# LB_BIT_i7-remoteTrigger_v03_2_2.net
KiCad netlist of a schematic drawn in EAGLE
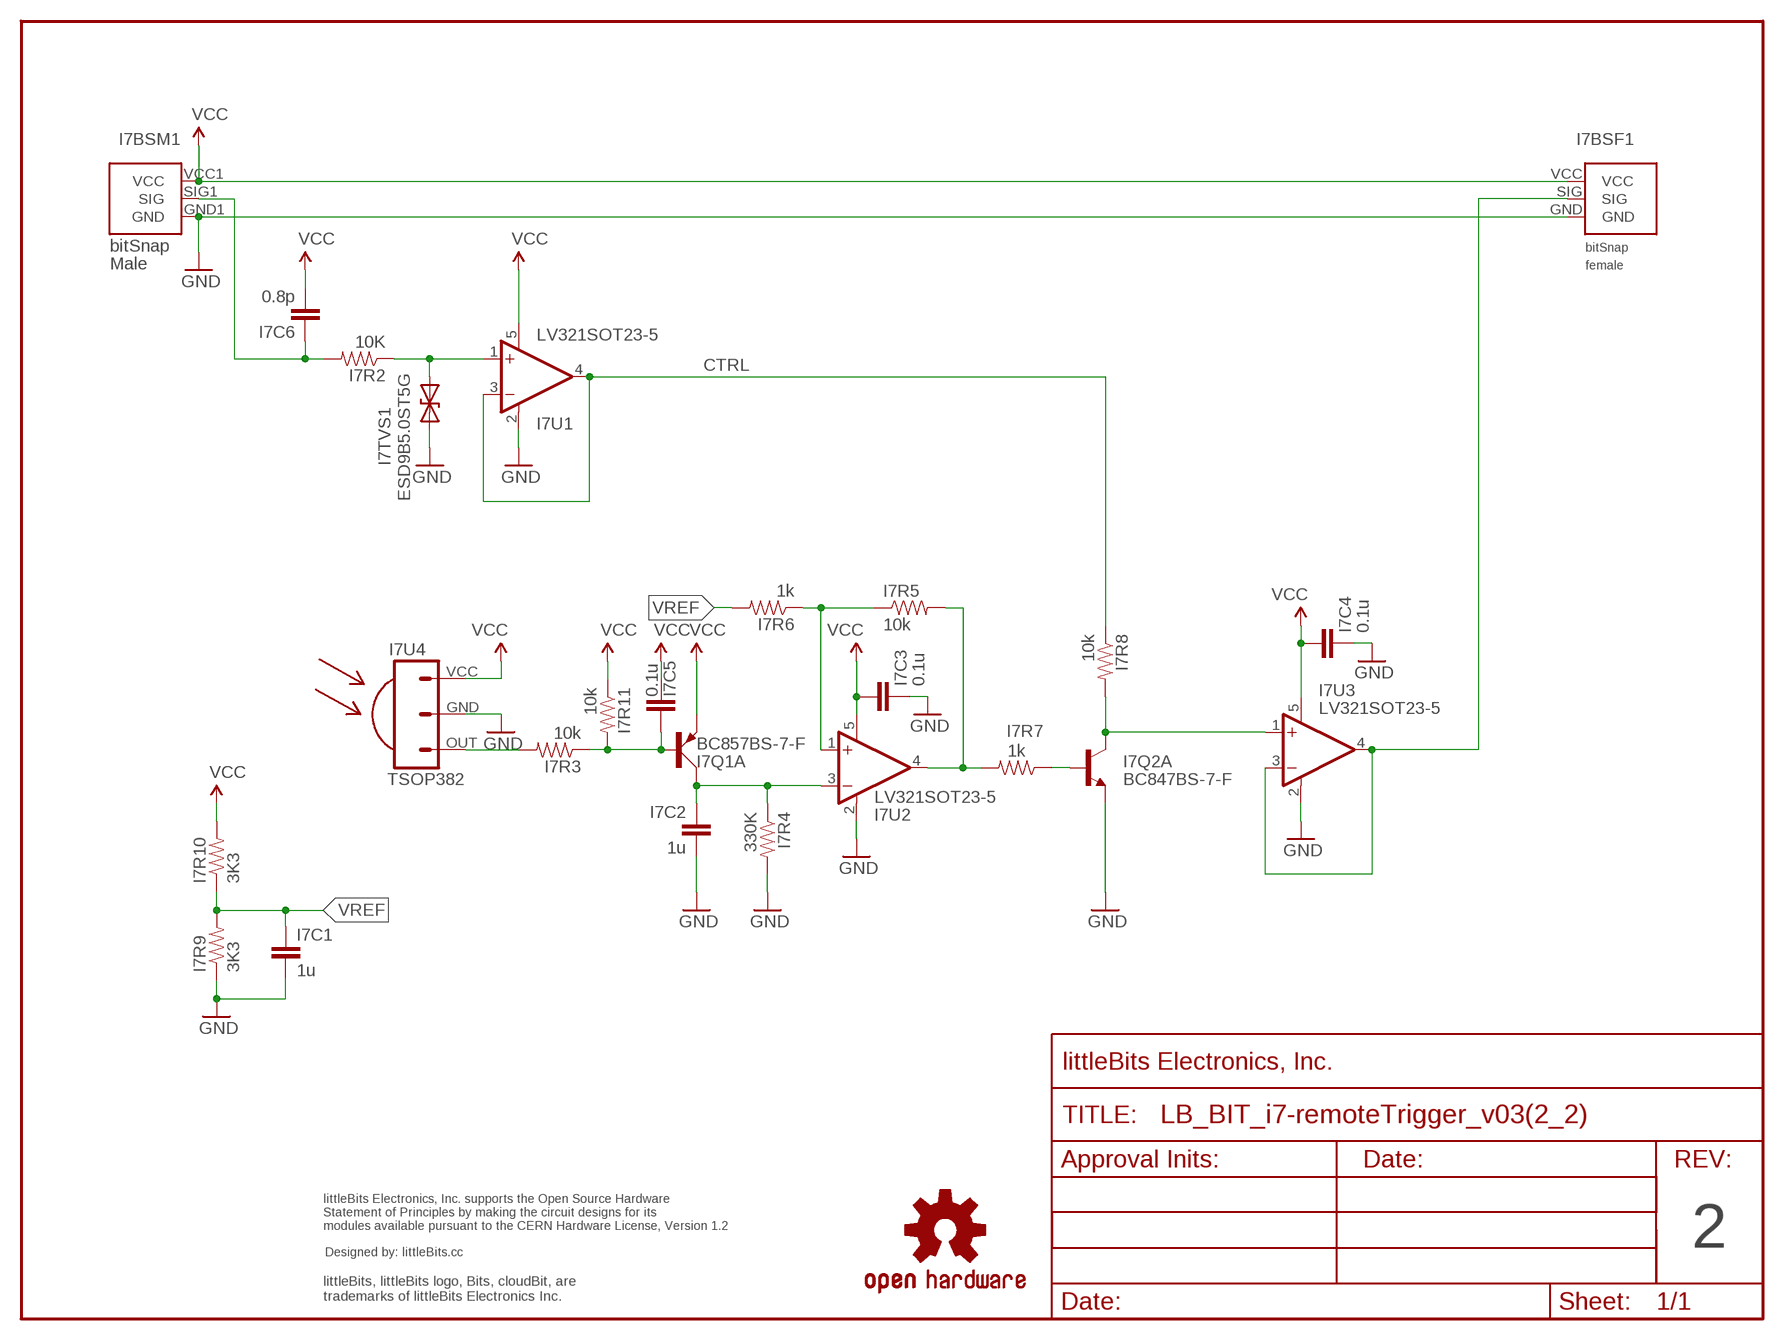
[diagram p0: schematic, sheet 1]

(export (version "E")
  (design (tool "Eeschema 10.0.6"))
  (components
    (comp (ref "I7BSF1")
      (value "BITSNAP_V03_FEMALE")
      (footprint "eagle-import:BITSNAP_V03_FEMALE")
      (libsource (lib "eagle-import") (part "BITSNAP_V03_FEMALE"))
    )
    (comp (ref "I7BSM1")
      (value "BITSNAP_V03_MALE")
      (footprint "eagle-import:BITSNAP_V03_MALE")
      (libsource (lib "eagle-import") (part "BITSNAP_V03_MALE"))
    )
    (comp (ref "I7C1")
      (value "1u")
      (footprint "eagle-import:CAP-0603")
      (libsource (lib "eagle-import") (part "CAPCAP-0603"))
    )
    (comp (ref "I7C2")
      (value "1u")
      (footprint "eagle-import:CAP-0603")
      (libsource (lib "eagle-import") (part "CAPCAP-0603"))
    )
    (comp (ref "I7C3")
      (value "0.1u")
      (footprint "eagle-import:CAP-0603")
      (libsource (lib "eagle-import") (part "CAPCAP-0603"))
    )
    (comp (ref "I7C4")
      (value "0.1u")
      (footprint "eagle-import:CAP-0603")
      (libsource (lib "eagle-import") (part "CAPCAP-0603"))
    )
    (comp (ref "I7C5")
      (value "0.1u")
      (footprint "eagle-import:CAP-0603")
      (libsource (lib "eagle-import") (part "CAPCAP-0603"))
    )
    (comp (ref "I7C6")
      (value "0.8p")
      (footprint "eagle-import:CAP-0603")
      (libsource (lib "eagle-import") (part "CAPCAP-0603"))
    )
    (comp (ref "I7Q1")
      (value "BC857BS-7-F")
      (footprint "eagle-import:SOT-363_PHILLIPS")
      (libsource (lib "eagle-import") (part "TRANS-BJT_PNP-DUALBC857"))
    )
    (comp (ref "I7Q2")
      (value "BC847BS-7-F")
      (footprint "eagle-import:SOT-363_PHILLIPS")
      (libsource (lib "eagle-import") (part "TRANS-BJT_NPN-DUAL-BC847BS"))
    )
    (comp (ref "I7R2")
      (value "10K")
      (footprint "eagle-import:RES-0603")
      (libsource (lib "eagle-import") (part "RESISTOR0603"))
    )
    (comp (ref "I7R3")
      (value "10k")
      (footprint "eagle-import:RES-0603")
      (libsource (lib "eagle-import") (part "RESISTOR0603"))
    )
    (comp (ref "I7R4")
      (value "330K")
      (footprint "eagle-import:RES-0603")
      (libsource (lib "eagle-import") (part "RESISTOR0603"))
    )
    (comp (ref "I7R5")
      (value "10k")
      (footprint "eagle-import:RES-0603")
      (libsource (lib "eagle-import") (part "RESISTOR0603"))
    )
    (comp (ref "I7R6")
      (value "1k")
      (footprint "eagle-import:RES-0603")
      (libsource (lib "eagle-import") (part "RESISTOR0603"))
    )
    (comp (ref "I7R7")
      (value "1k")
      (footprint "eagle-import:RES-0603")
      (libsource (lib "eagle-import") (part "RESISTOR0603"))
    )
    (comp (ref "I7R8")
      (value "10k")
      (footprint "eagle-import:RES-0603")
      (libsource (lib "eagle-import") (part "RESISTOR0603"))
    )
    (comp (ref "I7R9")
      (value "3K3")
      (footprint "eagle-import:RES-0603")
      (libsource (lib "eagle-import") (part "RESISTOR0603"))
    )
    (comp (ref "I7R10")
      (value "3K3")
      (footprint "eagle-import:RES-0603")
      (libsource (lib "eagle-import") (part "RESISTOR0603"))
    )
    (comp (ref "I7R11")
      (value "10k")
      (footprint "eagle-import:RES-0603")
      (libsource (lib "eagle-import") (part "RESISTOR0603"))
    )
    (comp (ref "I7TVS1")
      (value "ESD9B5.0ST5G")
      (footprint "eagle-import:SOD-923")
      (libsource (lib "eagle-import") (part "DIODE-TVSSOD-923"))
    )
    (comp (ref "I7U1")
      (value "LV321SOT23-5")
      (footprint "eagle-import:SOT23-5")
      (libsource (lib "eagle-import") (part "LV321SOT23-5"))
    )
    (comp (ref "I7U2")
      (value "LV321SOT23-5")
      (footprint "eagle-import:SOT23-5")
      (libsource (lib "eagle-import") (part "LV321SOT23-5"))
    )
    (comp (ref "I7U3")
      (value "LV321SOT23-5")
      (footprint "eagle-import:SOT23-5")
      (libsource (lib "eagle-import") (part "LV321SOT23-5"))
    )
    (comp (ref "I7U4")
      (value "TSOP382")
      (footprint "eagle-import:IR-RECEIVER-TSOP382-THRU-HOLE")
      (libsource (lib "eagle-import") (part "TSOP38238-IR-RECEIVER-MODULE"))
    )
    (comp (ref "U$2")
      (value "OSHWCREDIT")
      (footprint "eagle-import:OSHWCREDIT")
      (libsource (lib "eagle-import") (part "OSHWCREDIT"))
    )
    (comp (ref "U$3")
      (value "OSHW-LOGOL")
      (footprint "eagle-import:OSHW-LOGO-L")
      (libsource (lib "eagle-import") (part "OSHW-LOGOL"))
    )
    (comp (ref "U$21")
      (value "FRAME-LETTER-OHWOHW")
      (footprint "eagle-import:FABDWG01-OHW")
      (libsource (lib "eagle-import") (part "FRAME-LETTER-OHWOHW"))
    )
  )
  (nets
    (net (code "1") (name "/CTRL") (class "Default")
      (node (ref "I7R8") (pin "1") (pinfunction "1_1") (pintype "passive"))
      (node (ref "I7U1") (pin "3") (pinfunction "-IN_3") (pintype "input"))
      (node (ref "I7U1") (pin "4") (pinfunction "OUT_4") (pintype "output"))
    )
    (net (code "2") (name "GND") (class "Default")
      (node (ref "I7BSF1") (pin "GND") (pinfunction "GND_GND") (pintype "bidirectional"))
      (node (ref "I7BSM1") (pin "GND1") (pinfunction "GND_GND1") (pintype "bidirectional"))
      (node (ref "I7C1") (pin "2") (pinfunction "2_2") (pintype "passive"))
      (node (ref "I7C2") (pin "2") (pinfunction "2_2") (pintype "passive"))
      (node (ref "I7C3") (pin "1") (pinfunction "1_1") (pintype "passive"))
      (node (ref "I7C4") (pin "1") (pinfunction "1_1") (pintype "passive"))
      (node (ref "I7Q2") (pin "1") (pinfunction "E_1") (pintype "passive"))
      (node (ref "I7R4") (pin "2") (pinfunction "2_2") (pintype "passive"))
      (node (ref "I7R9") (pin "1") (pinfunction "1_1") (pintype "passive"))
      (node (ref "I7TVS1") (pin "1") (pinfunction "A_1") (pintype "passive"))
      (node (ref "I7U1") (pin "2") (pinfunction "V-_2") (pintype "power_in"))
      (node (ref "I7U2") (pin "2") (pinfunction "V-_2") (pintype "power_in"))
      (node (ref "I7U3") (pin "2") (pinfunction "V-_2") (pintype "power_in"))
      (node (ref "I7U4") (pin "GND") (pinfunction "GND_GND") (pintype "passive"))
    )
    (net (code "3") (name "Net-(I7BSM1-SIG)") (class "Default")
      (node (ref "I7BSM1") (pin "SIG1") (pinfunction "SIG_SIG1") (pintype "bidirectional"))
      (node (ref "I7C6") (pin "1") (pinfunction "1_1") (pintype "passive"))
      (node (ref "I7R2") (pin "2") (pinfunction "2_2") (pintype "passive"))
    )
    (net (code "4") (name "Net-(I7Q1A-B)") (class "Default")
      (node (ref "I7C5") (pin "2") (pinfunction "2_2") (pintype "passive"))
      (node (ref "I7Q1") (pin "2") (pinfunction "B_2") (pintype "passive"))
      (node (ref "I7R11") (pin "2") (pinfunction "2_2") (pintype "passive"))
      (node (ref "I7R3") (pin "1") (pinfunction "1_1") (pintype "passive"))
    )
    (net (code "5") (name "Net-(I7Q1A-C)") (class "Default")
      (node (ref "I7C2") (pin "1") (pinfunction "1_1") (pintype "passive"))
      (node (ref "I7Q1") (pin "6") (pinfunction "C_6") (pintype "passive"))
      (node (ref "I7R4") (pin "1") (pinfunction "1_1") (pintype "passive"))
      (node (ref "I7U2") (pin "3") (pinfunction "-IN_3") (pintype "input"))
    )
    (net (code "6") (name "Net-(I7Q2A-B)") (class "Default")
      (node (ref "I7Q2") (pin "2") (pinfunction "B_2") (pintype "passive"))
      (node (ref "I7R7") (pin "1") (pinfunction "1_1") (pintype "passive"))
    )
    (net (code "7") (name "Net-(I7Q2A-C)") (class "Default")
      (node (ref "I7Q2") (pin "6") (pinfunction "C_6") (pintype "passive"))
      (node (ref "I7R8") (pin "2") (pinfunction "2_2") (pintype "passive"))
      (node (ref "I7U3") (pin "1") (pinfunction "+IN_1") (pintype "input"))
    )
    (net (code "8") (name "Net-(I7R3-Pad2)") (class "Default")
      (node (ref "I7R3") (pin "2") (pinfunction "2_2") (pintype "passive"))
      (node (ref "I7U4") (pin "OUT") (pinfunction "OUT_OUT") (pintype "passive"))
    )
    (net (code "9") (name "Net-(I7TVS1-C)") (class "Default")
      (node (ref "I7R2") (pin "1") (pinfunction "1_1") (pintype "passive"))
      (node (ref "I7TVS1") (pin "2") (pinfunction "C_2") (pintype "passive"))
      (node (ref "I7U1") (pin "1") (pinfunction "+IN_1") (pintype "input"))
    )
    (net (code "10") (name "Net-(I7U2-+IN)") (class "Default")
      (node (ref "I7R5") (pin "1") (pinfunction "1_1") (pintype "passive"))
      (node (ref "I7R6") (pin "1") (pinfunction "1_1") (pintype "passive"))
      (node (ref "I7U2") (pin "1") (pinfunction "+IN_1") (pintype "input"))
    )
    (net (code "11") (name "Net-(I7U2-OUT)") (class "Default")
      (node (ref "I7R5") (pin "2") (pinfunction "2_2") (pintype "passive"))
      (node (ref "I7R7") (pin "2") (pinfunction "2_2") (pintype "passive"))
      (node (ref "I7U2") (pin "4") (pinfunction "OUT_4") (pintype "output"))
    )
    (net (code "12") (name "Net-(I7U3--IN)") (class "Default")
      (node (ref "I7BSF1") (pin "SIG") (pinfunction "SIG_SIG") (pintype "bidirectional"))
      (node (ref "I7U3") (pin "3") (pinfunction "-IN_3") (pintype "input"))
      (node (ref "I7U3") (pin "4") (pinfunction "OUT_4") (pintype "output"))
    )
    (net (code "13") (name "VCC") (class "Default")
      (node (ref "I7BSF1") (pin "VCC") (pinfunction "VCC_VCC") (pintype "bidirectional"))
      (node (ref "I7BSM1") (pin "VCC1") (pinfunction "VCC_VCC1") (pintype "bidirectional"))
      (node (ref "I7C3") (pin "2") (pinfunction "2_2") (pintype "passive"))
      (node (ref "I7C4") (pin "2") (pinfunction "2_2") (pintype "passive"))
      (node (ref "I7C5") (pin "1") (pinfunction "1_1") (pintype "passive"))
      (node (ref "I7C6") (pin "2") (pinfunction "2_2") (pintype "passive"))
      (node (ref "I7Q1") (pin "1") (pinfunction "E_1") (pintype "passive"))
      (node (ref "I7R10") (pin "2") (pinfunction "2_2") (pintype "passive"))
      (node (ref "I7R11") (pin "1") (pinfunction "1_1") (pintype "passive"))
      (node (ref "I7U1") (pin "5") (pinfunction "V+_5") (pintype "power_in"))
      (node (ref "I7U2") (pin "5") (pinfunction "V+_5") (pintype "power_in"))
      (node (ref "I7U3") (pin "5") (pinfunction "V+_5") (pintype "power_in"))
      (node (ref "I7U4") (pin "VCC") (pinfunction "VCC_VCC") (pintype "passive"))
    )
    (net (code "14") (name "VREF") (class "Default")
      (node (ref "I7C1") (pin "1") (pinfunction "1_1") (pintype "passive"))
      (node (ref "I7R10") (pin "1") (pinfunction "1_1") (pintype "passive"))
      (node (ref "I7R6") (pin "2") (pinfunction "2_2") (pintype "passive"))
      (node (ref "I7R9") (pin "2") (pinfunction "2_2") (pintype "passive"))
    )
  )
)
